# 128.net
KiCad netlist of a schematic drawn in EAGLE
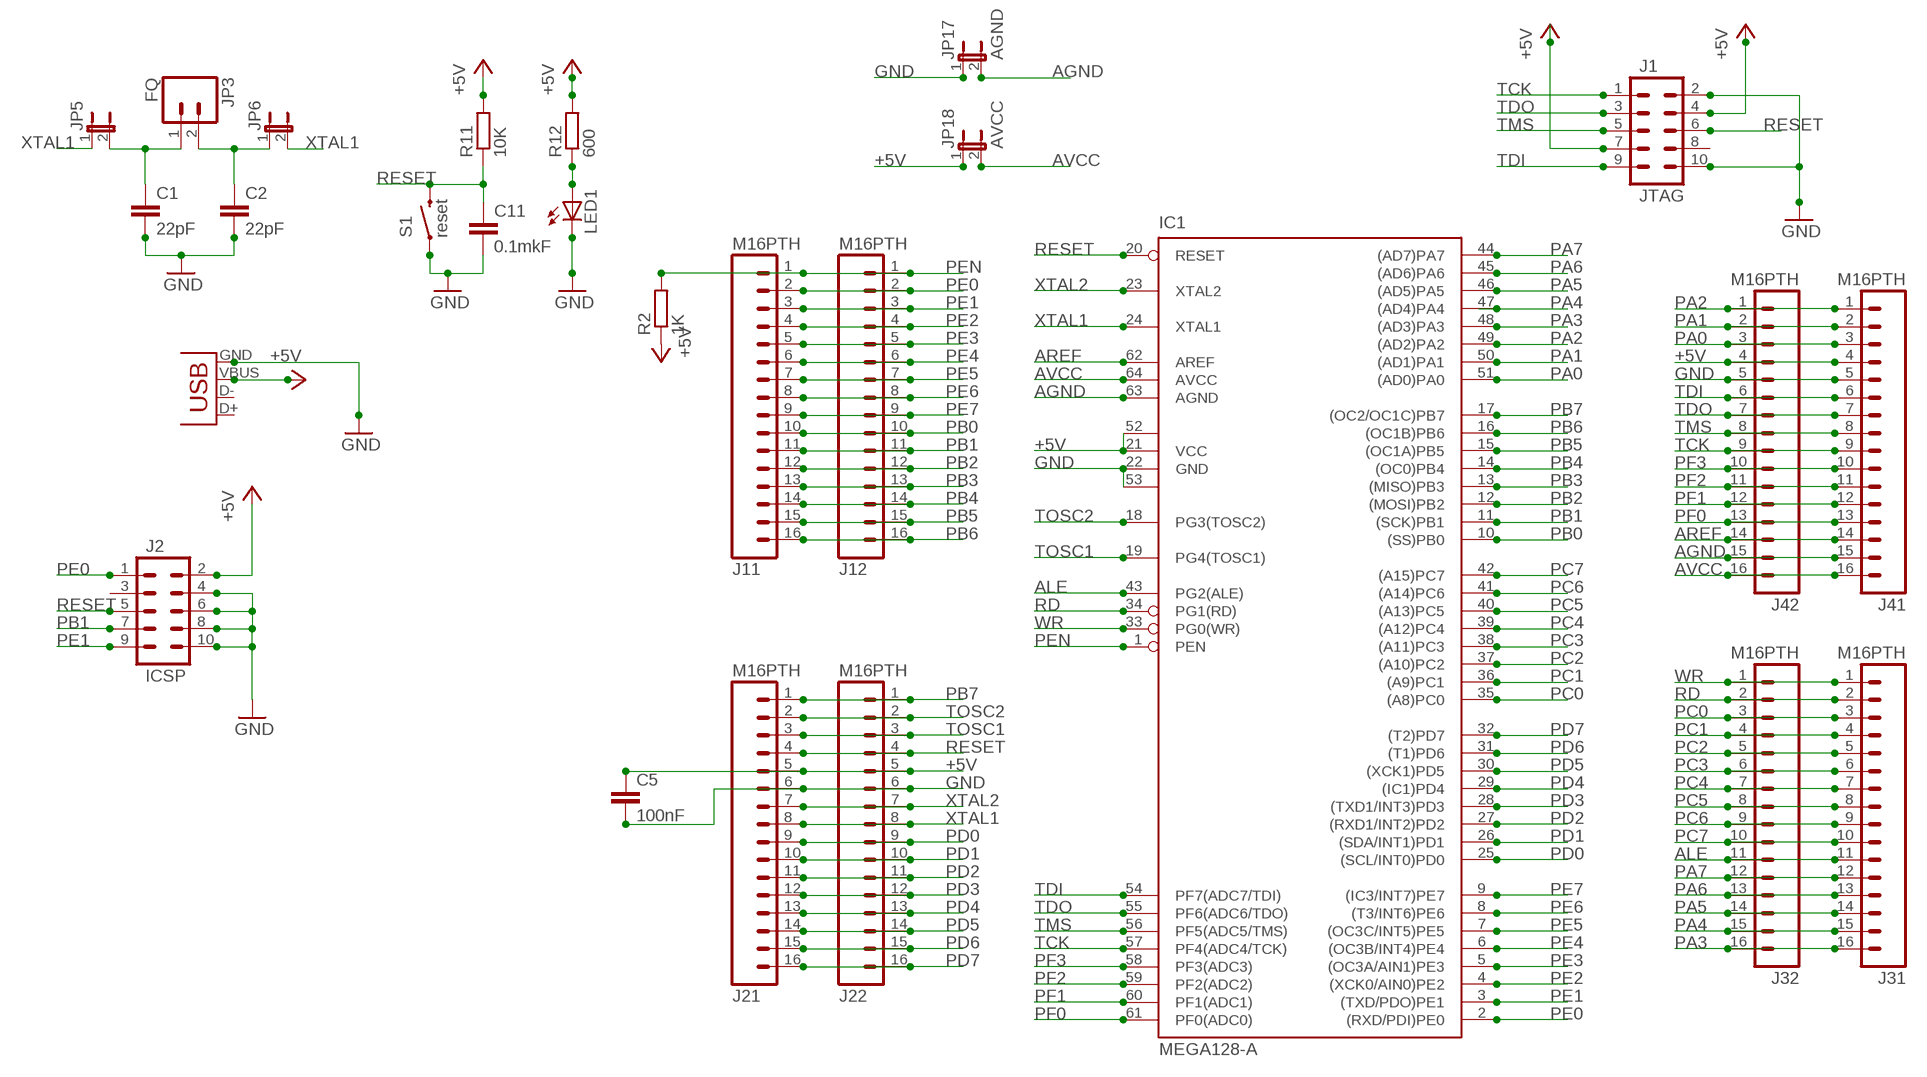
[diagram p0: schematic, sheet 1]

(export (version "E")
  (design (tool "Eeschema 10.0.6"))
  (components
    (comp (ref "C1")
      (value "22pF")
      (footprint "eagle-import:C0805")
      (libsource (lib "eagle-import") (part "C-EUC0805"))
    )
    (comp (ref "C2")
      (value "22pF")
      (footprint "eagle-import:C0805")
      (libsource (lib "eagle-import") (part "C-EUC0805"))
    )
    (comp (ref "C5")
      (value "100nF")
      (footprint "eagle-import:C0805")
      (libsource (lib "eagle-import") (part "C-EUC0805"))
    )
    (comp (ref "C11")
      (value "0.1mkF")
      (footprint "eagle-import:C0805")
      (libsource (lib "eagle-import") (part "C-EUC0805"))
    )
    (comp (ref "IC1")
      (value "MEGA128-A")
      (footprint "eagle-import:TQFP64")
      (libsource (lib "eagle-import") (part "MEGA128-A"))
    )
    (comp (ref "J1")
      (value "JTAG")
      (footprint "eagle-import:2X5-SHROUDED_LOCK")
      (libsource (lib "eagle-import") (part "M05X2SHD_LOCK"))
    )
    (comp (ref "J2")
      (value "ICSP")
      (footprint "eagle-import:2X5-SHROUDED_LOCK")
      (libsource (lib "eagle-import") (part "M05X2SHD_LOCK"))
    )
    (comp (ref "J11")
      (value "M16PTH")
      (footprint "eagle-import:1X16")
      (libsource (lib "eagle-import") (part "M16PTH"))
    )
    (comp (ref "J12")
      (value "M16PTH")
      (footprint "eagle-import:1X16")
      (libsource (lib "eagle-import") (part "M16PTH"))
    )
    (comp (ref "J21")
      (value "M16PTH")
      (footprint "eagle-import:1X16")
      (libsource (lib "eagle-import") (part "M16PTH"))
    )
    (comp (ref "J22")
      (value "M16PTH")
      (footprint "eagle-import:1X16")
      (libsource (lib "eagle-import") (part "M16PTH"))
    )
    (comp (ref "J31")
      (value "M16PTH")
      (footprint "eagle-import:1X16")
      (libsource (lib "eagle-import") (part "M16PTH"))
    )
    (comp (ref "J32")
      (value "M16PTH")
      (footprint "eagle-import:1X16")
      (libsource (lib "eagle-import") (part "M16PTH"))
    )
    (comp (ref "J41")
      (value "M16PTH")
      (footprint "eagle-import:1X16")
      (libsource (lib "eagle-import") (part "M16PTH"))
    )
    (comp (ref "J42")
      (value "M16PTH")
      (footprint "eagle-import:1X16")
      (libsource (lib "eagle-import") (part "M16PTH"))
    )
    (comp (ref "JP3")
      (value "FQ")
      (footprint "eagle-import:1X02_LOCK")
      (libsource (lib "eagle-import") (part "M02LOCK"))
    )
    (comp (ref "JP4")
      (value "USBSMD")
      (footprint "eagle-import:USB-MINIB")
      (libsource (lib "eagle-import") (part "USBSMD"))
    )
    (comp (ref "JP5")
      (value "JUMPER-2PTH")
      (footprint "eagle-import:1X02")
      (libsource (lib "eagle-import") (part "JUMPER-2PTH"))
    )
    (comp (ref "JP6")
      (value "JUMPER-2PTH")
      (footprint "eagle-import:1X02")
      (libsource (lib "eagle-import") (part "JUMPER-2PTH"))
    )
    (comp (ref "JP17")
      (value "AGND")
      (footprint "eagle-import:1X02")
      (libsource (lib "eagle-import") (part "JUMPER-2PTH"))
    )
    (comp (ref "JP18")
      (value "AVCC")
      (footprint "eagle-import:1X02")
      (libsource (lib "eagle-import") (part "JUMPER-2PTH"))
    )
    (comp (ref "LED1")
      (value "LED1206")
      (footprint "eagle-import:LED-1206")
      (libsource (lib "eagle-import") (part "LED1206"))
    )
    (comp (ref "R2")
      (value "1K")
      (footprint "eagle-import:R0805")
      (libsource (lib "eagle-import") (part "R-EU_R0805"))
    )
    (comp (ref "R11")
      (value "10K")
      (footprint "eagle-import:R0805")
      (libsource (lib "eagle-import") (part "R-EU_R0805"))
    )
    (comp (ref "R12")
      (value "600")
      (footprint "eagle-import:R0805")
      (libsource (lib "eagle-import") (part "R-EU_R0805"))
    )
    (comp (ref "S1")
      (value "reset")
      (footprint "eagle-import:TACTILE_SWITCH_SMD-2")
      (libsource (lib "eagle-import") (part "SWITCH-MOMENTARY-2SMD-2"))
    )
  )
  (nets
    (net (code "1") (name "+5V") (class "Default")
      (node (ref "C5") (pin "1") (pinfunction "1_1") (pintype "passive"))
      (node (ref "IC1") (pin "21") (pinfunction "VCC_21") (pintype "power_in"))
      (node (ref "IC1") (pin "52") (pinfunction "VCC1_52") (pintype "power_in"))
      (node (ref "J1") (pin "4") (pinfunction "4_4") (pintype "passive"))
      (node (ref "J1") (pin "7") (pinfunction "7_7") (pintype "passive"))
      (node (ref "J2") (pin "2") (pinfunction "2_2") (pintype "passive"))
      (node (ref "J21") (pin "5") (pinfunction "5_5") (pintype "passive"))
      (node (ref "J22") (pin "5") (pinfunction "5_5") (pintype "passive"))
      (node (ref "J41") (pin "4") (pinfunction "4_4") (pintype "passive"))
      (node (ref "J42") (pin "4") (pinfunction "4_4") (pintype "passive"))
      (node (ref "JP18") (pin "1") (pinfunction "1_1") (pintype "passive"))
      (node (ref "JP4") (pin "VBUS") (pinfunction "VBUS_VBUS") (pintype "bidirectional"))
      (node (ref "R11") (pin "2") (pinfunction "2_2") (pintype "passive"))
      (node (ref "R12") (pin "2") (pinfunction "2_2") (pintype "passive"))
      (node (ref "R2") (pin "1") (pinfunction "1_1") (pintype "passive"))
    )
    (net (code "2") (name "/AGND") (class "Default")
      (node (ref "IC1") (pin "63") (pinfunction "AGND_63") (pintype "bidirectional"))
      (node (ref "J41") (pin "15") (pinfunction "15_15") (pintype "passive"))
      (node (ref "J42") (pin "15") (pinfunction "15_15") (pintype "passive"))
      (node (ref "JP17") (pin "2") (pinfunction "2_2") (pintype "passive"))
    )
    (net (code "3") (name "/ALE") (class "Default")
      (node (ref "IC1") (pin "43") (pinfunction "PG2(ALE)_43") (pintype "bidirectional"))
      (node (ref "J31") (pin "11") (pinfunction "11_11") (pintype "passive"))
      (node (ref "J32") (pin "11") (pinfunction "11_11") (pintype "passive"))
    )
    (net (code "4") (name "/AREF") (class "Default")
      (node (ref "IC1") (pin "62") (pinfunction "AREF_62") (pintype "bidirectional"))
      (node (ref "J41") (pin "14") (pinfunction "14_14") (pintype "passive"))
      (node (ref "J42") (pin "14") (pinfunction "14_14") (pintype "passive"))
    )
    (net (code "5") (name "/AVCC") (class "Default")
      (node (ref "IC1") (pin "64") (pinfunction "AVCC_64") (pintype "bidirectional"))
      (node (ref "J41") (pin "16") (pinfunction "16_16") (pintype "passive"))
      (node (ref "J42") (pin "16") (pinfunction "16_16") (pintype "passive"))
      (node (ref "JP18") (pin "2") (pinfunction "2_2") (pintype "passive"))
    )
    (net (code "6") (name "/PA0") (class "Default")
      (node (ref "IC1") (pin "51") (pinfunction "(AD0)PA0_51") (pintype "bidirectional"))
      (node (ref "J41") (pin "3") (pinfunction "3_3") (pintype "passive"))
      (node (ref "J42") (pin "3") (pinfunction "3_3") (pintype "passive"))
    )
    (net (code "7") (name "/PA1") (class "Default")
      (node (ref "IC1") (pin "50") (pinfunction "(AD1)PA1_50") (pintype "bidirectional"))
      (node (ref "J41") (pin "2") (pinfunction "2_2") (pintype "passive"))
      (node (ref "J42") (pin "2") (pinfunction "2_2") (pintype "passive"))
    )
    (net (code "8") (name "/PA2") (class "Default")
      (node (ref "IC1") (pin "49") (pinfunction "(AD2)PA2_49") (pintype "bidirectional"))
      (node (ref "J41") (pin "1") (pinfunction "1_1") (pintype "passive"))
      (node (ref "J42") (pin "1") (pinfunction "1_1") (pintype "passive"))
    )
    (net (code "9") (name "/PA3") (class "Default")
      (node (ref "IC1") (pin "48") (pinfunction "(AD3)PA3_48") (pintype "bidirectional"))
      (node (ref "J31") (pin "16") (pinfunction "16_16") (pintype "passive"))
      (node (ref "J32") (pin "16") (pinfunction "16_16") (pintype "passive"))
    )
    (net (code "10") (name "/PA4") (class "Default")
      (node (ref "IC1") (pin "47") (pinfunction "(AD4)PA4_47") (pintype "bidirectional"))
      (node (ref "J31") (pin "15") (pinfunction "15_15") (pintype "passive"))
      (node (ref "J32") (pin "15") (pinfunction "15_15") (pintype "passive"))
    )
    (net (code "11") (name "/PA5") (class "Default")
      (node (ref "IC1") (pin "46") (pinfunction "(AD5)PA5_46") (pintype "bidirectional"))
      (node (ref "J31") (pin "14") (pinfunction "14_14") (pintype "passive"))
      (node (ref "J32") (pin "14") (pinfunction "14_14") (pintype "passive"))
    )
    (net (code "12") (name "/PA6") (class "Default")
      (node (ref "IC1") (pin "45") (pinfunction "(AD6)PA6_45") (pintype "bidirectional"))
      (node (ref "J31") (pin "13") (pinfunction "13_13") (pintype "passive"))
      (node (ref "J32") (pin "13") (pinfunction "13_13") (pintype "passive"))
    )
    (net (code "13") (name "/PA7") (class "Default")
      (node (ref "IC1") (pin "44") (pinfunction "(AD7)PA7_44") (pintype "bidirectional"))
      (node (ref "J31") (pin "12") (pinfunction "12_12") (pintype "passive"))
      (node (ref "J32") (pin "12") (pinfunction "12_12") (pintype "passive"))
    )
    (net (code "14") (name "/PB0") (class "Default")
      (node (ref "IC1") (pin "10") (pinfunction "(SS)PB0_10") (pintype "bidirectional"))
      (node (ref "J11") (pin "10") (pinfunction "10_10") (pintype "passive"))
      (node (ref "J12") (pin "10") (pinfunction "10_10") (pintype "passive"))
    )
    (net (code "15") (name "/PB1") (class "Default")
      (node (ref "IC1") (pin "11") (pinfunction "(SCK)PB1_11") (pintype "bidirectional"))
      (node (ref "J11") (pin "11") (pinfunction "11_11") (pintype "passive"))
      (node (ref "J12") (pin "11") (pinfunction "11_11") (pintype "passive"))
      (node (ref "J2") (pin "7") (pinfunction "7_7") (pintype "passive"))
    )
    (net (code "16") (name "/PB2") (class "Default")
      (node (ref "IC1") (pin "12") (pinfunction "(MOSI)PB2_12") (pintype "bidirectional"))
      (node (ref "J11") (pin "12") (pinfunction "12_12") (pintype "passive"))
      (node (ref "J12") (pin "12") (pinfunction "12_12") (pintype "passive"))
    )
    (net (code "17") (name "/PB3") (class "Default")
      (node (ref "IC1") (pin "13") (pinfunction "(MISO)PB3_13") (pintype "bidirectional"))
      (node (ref "J11") (pin "13") (pinfunction "13_13") (pintype "passive"))
      (node (ref "J12") (pin "13") (pinfunction "13_13") (pintype "passive"))
    )
    (net (code "18") (name "/PB4") (class "Default")
      (node (ref "IC1") (pin "14") (pinfunction "(OC0)PB4_14") (pintype "bidirectional"))
      (node (ref "J11") (pin "14") (pinfunction "14_14") (pintype "passive"))
      (node (ref "J12") (pin "14") (pinfunction "14_14") (pintype "passive"))
    )
    (net (code "19") (name "/PB5") (class "Default")
      (node (ref "IC1") (pin "15") (pinfunction "(OC1A)PB5_15") (pintype "bidirectional"))
      (node (ref "J11") (pin "15") (pinfunction "15_15") (pintype "passive"))
      (node (ref "J12") (pin "15") (pinfunction "15_15") (pintype "passive"))
    )
    (net (code "20") (name "/PB6") (class "Default")
      (node (ref "IC1") (pin "16") (pinfunction "(OC1B)PB6_16") (pintype "bidirectional"))
      (node (ref "J11") (pin "16") (pinfunction "16_16") (pintype "passive"))
      (node (ref "J12") (pin "16") (pinfunction "16_16") (pintype "passive"))
    )
    (net (code "21") (name "/PB7") (class "Default")
      (node (ref "IC1") (pin "17") (pinfunction "(OC2/OC1C)PB7_17") (pintype "bidirectional"))
      (node (ref "J21") (pin "1") (pinfunction "1_1") (pintype "passive"))
      (node (ref "J22") (pin "1") (pinfunction "1_1") (pintype "passive"))
    )
    (net (code "22") (name "/PC0") (class "Default")
      (node (ref "IC1") (pin "35") (pinfunction "(A8)PC0_35") (pintype "output"))
      (node (ref "J31") (pin "3") (pinfunction "3_3") (pintype "passive"))
      (node (ref "J32") (pin "3") (pinfunction "3_3") (pintype "passive"))
    )
    (net (code "23") (name "/PC1") (class "Default")
      (node (ref "IC1") (pin "36") (pinfunction "(A9)PC1_36") (pintype "output"))
      (node (ref "J31") (pin "4") (pinfunction "4_4") (pintype "passive"))
      (node (ref "J32") (pin "4") (pinfunction "4_4") (pintype "passive"))
    )
    (net (code "24") (name "/PC2") (class "Default")
      (node (ref "IC1") (pin "37") (pinfunction "(A10)PC2_37") (pintype "output"))
      (node (ref "J31") (pin "5") (pinfunction "5_5") (pintype "passive"))
      (node (ref "J32") (pin "5") (pinfunction "5_5") (pintype "passive"))
    )
    (net (code "25") (name "/PC3") (class "Default")
      (node (ref "IC1") (pin "38") (pinfunction "(A11)PC3_38") (pintype "output"))
      (node (ref "J31") (pin "6") (pinfunction "6_6") (pintype "passive"))
      (node (ref "J32") (pin "6") (pinfunction "6_6") (pintype "passive"))
    )
    (net (code "26") (name "/PC4") (class "Default")
      (node (ref "IC1") (pin "39") (pinfunction "(A12)PC4_39") (pintype "output"))
      (node (ref "J31") (pin "7") (pinfunction "7_7") (pintype "passive"))
      (node (ref "J32") (pin "7") (pinfunction "7_7") (pintype "passive"))
    )
    (net (code "27") (name "/PC5") (class "Default")
      (node (ref "IC1") (pin "40") (pinfunction "(A13)PC5_40") (pintype "output"))
      (node (ref "J31") (pin "8") (pinfunction "8_8") (pintype "passive"))
      (node (ref "J32") (pin "8") (pinfunction "8_8") (pintype "passive"))
    )
    (net (code "28") (name "/PC6") (class "Default")
      (node (ref "IC1") (pin "41") (pinfunction "(A14)PC6_41") (pintype "output"))
      (node (ref "J31") (pin "9") (pinfunction "9_9") (pintype "passive"))
      (node (ref "J32") (pin "9") (pinfunction "9_9") (pintype "passive"))
    )
    (net (code "29") (name "/PC7") (class "Default")
      (node (ref "IC1") (pin "42") (pinfunction "(A15)PC7_42") (pintype "output"))
      (node (ref "J31") (pin "10") (pinfunction "10_10") (pintype "passive"))
      (node (ref "J32") (pin "10") (pinfunction "10_10") (pintype "passive"))
    )
    (net (code "30") (name "/PD0") (class "Default")
      (node (ref "IC1") (pin "25") (pinfunction "(SCL/INT0)PD0_25") (pintype "bidirectional"))
      (node (ref "J21") (pin "9") (pinfunction "9_9") (pintype "passive"))
      (node (ref "J22") (pin "9") (pinfunction "9_9") (pintype "passive"))
    )
    (net (code "31") (name "/PD1") (class "Default")
      (node (ref "IC1") (pin "26") (pinfunction "(SDA/INT1)PD1_26") (pintype "bidirectional"))
      (node (ref "J21") (pin "10") (pinfunction "10_10") (pintype "passive"))
      (node (ref "J22") (pin "10") (pinfunction "10_10") (pintype "passive"))
    )
    (net (code "32") (name "/PD2") (class "Default")
      (node (ref "IC1") (pin "27") (pinfunction "(RXD1/INT2)PD2_27") (pintype "bidirectional"))
      (node (ref "J21") (pin "11") (pinfunction "11_11") (pintype "passive"))
      (node (ref "J22") (pin "11") (pinfunction "11_11") (pintype "passive"))
    )
    (net (code "33") (name "/PD3") (class "Default")
      (node (ref "IC1") (pin "28") (pinfunction "(TXD1/INT3)PD3_28") (pintype "bidirectional"))
      (node (ref "J21") (pin "12") (pinfunction "12_12") (pintype "passive"))
      (node (ref "J22") (pin "12") (pinfunction "12_12") (pintype "passive"))
    )
    (net (code "34") (name "/PD4") (class "Default")
      (node (ref "IC1") (pin "29") (pinfunction "(IC1)PD4_29") (pintype "bidirectional"))
      (node (ref "J21") (pin "13") (pinfunction "13_13") (pintype "passive"))
      (node (ref "J22") (pin "13") (pinfunction "13_13") (pintype "passive"))
    )
    (net (code "35") (name "/PD5") (class "Default")
      (node (ref "IC1") (pin "30") (pinfunction "(XCK1)PD5_30") (pintype "bidirectional"))
      (node (ref "J21") (pin "14") (pinfunction "14_14") (pintype "passive"))
      (node (ref "J22") (pin "14") (pinfunction "14_14") (pintype "passive"))
    )
    (net (code "36") (name "/PD6") (class "Default")
      (node (ref "IC1") (pin "31") (pinfunction "(T1)PD6_31") (pintype "bidirectional"))
      (node (ref "J21") (pin "15") (pinfunction "15_15") (pintype "passive"))
      (node (ref "J22") (pin "15") (pinfunction "15_15") (pintype "passive"))
    )
    (net (code "37") (name "/PD7") (class "Default")
      (node (ref "IC1") (pin "32") (pinfunction "(T2)PD7_32") (pintype "bidirectional"))
      (node (ref "J21") (pin "16") (pinfunction "16_16") (pintype "passive"))
      (node (ref "J22") (pin "16") (pinfunction "16_16") (pintype "passive"))
    )
    (net (code "38") (name "/PE0") (class "Default")
      (node (ref "IC1") (pin "2") (pinfunction "(RXD/PDI)PE0_2") (pintype "bidirectional"))
      (node (ref "J11") (pin "2") (pinfunction "2_2") (pintype "passive"))
      (node (ref "J12") (pin "2") (pinfunction "2_2") (pintype "passive"))
      (node (ref "J2") (pin "1") (pinfunction "1_1") (pintype "passive"))
    )
    (net (code "39") (name "/PE1") (class "Default")
      (node (ref "IC1") (pin "3") (pinfunction "(TXD/PDO)PE1_3") (pintype "bidirectional"))
      (node (ref "J11") (pin "3") (pinfunction "3_3") (pintype "passive"))
      (node (ref "J12") (pin "3") (pinfunction "3_3") (pintype "passive"))
      (node (ref "J2") (pin "9") (pinfunction "9_9") (pintype "passive"))
    )
    (net (code "40") (name "/PE2") (class "Default")
      (node (ref "IC1") (pin "4") (pinfunction "(XCK0/AIN0)PE2_4") (pintype "bidirectional"))
      (node (ref "J11") (pin "4") (pinfunction "4_4") (pintype "passive"))
      (node (ref "J12") (pin "4") (pinfunction "4_4") (pintype "passive"))
    )
    (net (code "41") (name "/PE3") (class "Default")
      (node (ref "IC1") (pin "5") (pinfunction "(OC3A/AIN1)PE3_5") (pintype "bidirectional"))
      (node (ref "J11") (pin "5") (pinfunction "5_5") (pintype "passive"))
      (node (ref "J12") (pin "5") (pinfunction "5_5") (pintype "passive"))
    )
    (net (code "42") (name "/PE4") (class "Default")
      (node (ref "IC1") (pin "6") (pinfunction "(OC3B/INT4)PE4_6") (pintype "bidirectional"))
      (node (ref "J11") (pin "6") (pinfunction "6_6") (pintype "passive"))
      (node (ref "J12") (pin "6") (pinfunction "6_6") (pintype "passive"))
    )
    (net (code "43") (name "/PE5") (class "Default")
      (node (ref "IC1") (pin "7") (pinfunction "(OC3C/INT5)PE5_7") (pintype "bidirectional"))
      (node (ref "J11") (pin "7") (pinfunction "7_7") (pintype "passive"))
      (node (ref "J12") (pin "7") (pinfunction "7_7") (pintype "passive"))
    )
    (net (code "44") (name "/PE6") (class "Default")
      (node (ref "IC1") (pin "8") (pinfunction "(T3/INT6)PE6_8") (pintype "bidirectional"))
      (node (ref "J11") (pin "8") (pinfunction "8_8") (pintype "passive"))
      (node (ref "J12") (pin "8") (pinfunction "8_8") (pintype "passive"))
    )
    (net (code "45") (name "/PE7") (class "Default")
      (node (ref "IC1") (pin "9") (pinfunction "(IC3/INT7)PE7_9") (pintype "bidirectional"))
      (node (ref "J11") (pin "9") (pinfunction "9_9") (pintype "passive"))
      (node (ref "J12") (pin "9") (pinfunction "9_9") (pintype "passive"))
    )
    (net (code "46") (name "/PEN") (class "Default")
      (node (ref "IC1") (pin "1") (pinfunction "PEN_1") (pintype "input"))
      (node (ref "J11") (pin "1") (pinfunction "1_1") (pintype "passive"))
      (node (ref "J12") (pin "1") (pinfunction "1_1") (pintype "passive"))
      (node (ref "R2") (pin "2") (pinfunction "2_2") (pintype "passive"))
    )
    (net (code "47") (name "/PF0") (class "Default")
      (node (ref "IC1") (pin "61") (pinfunction "PF0(ADC0)_61") (pintype "input"))
      (node (ref "J41") (pin "13") (pinfunction "13_13") (pintype "passive"))
      (node (ref "J42") (pin "13") (pinfunction "13_13") (pintype "passive"))
    )
    (net (code "48") (name "/PF1") (class "Default")
      (node (ref "IC1") (pin "60") (pinfunction "PF1(ADC1)_60") (pintype "input"))
      (node (ref "J41") (pin "12") (pinfunction "12_12") (pintype "passive"))
      (node (ref "J42") (pin "12") (pinfunction "12_12") (pintype "passive"))
    )
    (net (code "49") (name "/PF2") (class "Default")
      (node (ref "IC1") (pin "59") (pinfunction "PF2(ADC2)_59") (pintype "input"))
      (node (ref "J41") (pin "11") (pinfunction "11_11") (pintype "passive"))
      (node (ref "J42") (pin "11") (pinfunction "11_11") (pintype "passive"))
    )
    (net (code "50") (name "/PF3") (class "Default")
      (node (ref "IC1") (pin "58") (pinfunction "PF3(ADC3)_58") (pintype "input"))
      (node (ref "J41") (pin "10") (pinfunction "10_10") (pintype "passive"))
      (node (ref "J42") (pin "10") (pinfunction "10_10") (pintype "passive"))
    )
    (net (code "51") (name "/RD") (class "Default")
      (node (ref "IC1") (pin "34") (pinfunction "PG1(RD)_34") (pintype "bidirectional"))
      (node (ref "J31") (pin "2") (pinfunction "2_2") (pintype "passive"))
      (node (ref "J32") (pin "2") (pinfunction "2_2") (pintype "passive"))
    )
    (net (code "52") (name "/RESET") (class "Default")
      (node (ref "C11") (pin "1") (pinfunction "1_1") (pintype "passive"))
      (node (ref "IC1") (pin "20") (pinfunction "RESET_20") (pintype "input"))
      (node (ref "J1") (pin "6") (pinfunction "6_6") (pintype "passive"))
      (node (ref "J2") (pin "5") (pinfunction "5_5") (pintype "passive"))
      (node (ref "J21") (pin "4") (pinfunction "4_4") (pintype "passive"))
      (node (ref "J22") (pin "4") (pinfunction "4_4") (pintype "passive"))
      (node (ref "R11") (pin "1") (pinfunction "1_1") (pintype "passive"))
      (node (ref "S1") (pin "1") (pinfunction "2_1") (pintype "passive"))
    )
    (net (code "53") (name "/TCK") (class "Default")
      (node (ref "IC1") (pin "57") (pinfunction "PF4(ADC4/TCK)_57") (pintype "input"))
      (node (ref "J1") (pin "1") (pinfunction "1_1") (pintype "passive"))
      (node (ref "J41") (pin "9") (pinfunction "9_9") (pintype "passive"))
      (node (ref "J42") (pin "9") (pinfunction "9_9") (pintype "passive"))
    )
    (net (code "54") (name "/TDI") (class "Default")
      (node (ref "IC1") (pin "54") (pinfunction "PF7(ADC7/TDI)_54") (pintype "input"))
      (node (ref "J1") (pin "9") (pinfunction "9_9") (pintype "passive"))
      (node (ref "J41") (pin "6") (pinfunction "6_6") (pintype "passive"))
      (node (ref "J42") (pin "6") (pinfunction "6_6") (pintype "passive"))
    )
    (net (code "55") (name "/TDO") (class "Default")
      (node (ref "IC1") (pin "55") (pinfunction "PF6(ADC6/TDO)_55") (pintype "input"))
      (node (ref "J1") (pin "3") (pinfunction "3_3") (pintype "passive"))
      (node (ref "J41") (pin "7") (pinfunction "7_7") (pintype "passive"))
      (node (ref "J42") (pin "7") (pinfunction "7_7") (pintype "passive"))
    )
    (net (code "56") (name "/TMS") (class "Default")
      (node (ref "IC1") (pin "56") (pinfunction "PF5(ADC5/TMS)_56") (pintype "input"))
      (node (ref "J1") (pin "5") (pinfunction "5_5") (pintype "passive"))
      (node (ref "J41") (pin "8") (pinfunction "8_8") (pintype "passive"))
      (node (ref "J42") (pin "8") (pinfunction "8_8") (pintype "passive"))
    )
    (net (code "57") (name "/TOSC1") (class "Default")
      (node (ref "IC1") (pin "19") (pinfunction "PG4(TOSC1)_19") (pintype "bidirectional"))
      (node (ref "J21") (pin "3") (pinfunction "3_3") (pintype "passive"))
      (node (ref "J22") (pin "3") (pinfunction "3_3") (pintype "passive"))
    )
    (net (code "58") (name "/TOSC2") (class "Default")
      (node (ref "IC1") (pin "18") (pinfunction "PG3(TOSC2)_18") (pintype "bidirectional"))
      (node (ref "J21") (pin "2") (pinfunction "2_2") (pintype "passive"))
      (node (ref "J22") (pin "2") (pinfunction "2_2") (pintype "passive"))
    )
    (net (code "59") (name "/WR") (class "Default")
      (node (ref "IC1") (pin "33") (pinfunction "PG0(WR)_33") (pintype "bidirectional"))
      (node (ref "J31") (pin "1") (pinfunction "1_1") (pintype "passive"))
      (node (ref "J32") (pin "1") (pinfunction "1_1") (pintype "passive"))
    )
    (net (code "60") (name "/XTAL1") (class "Default")
      (node (ref "IC1") (pin "24") (pinfunction "XTAL1_24") (pintype "bidirectional"))
      (node (ref "J21") (pin "8") (pinfunction "8_8") (pintype "passive"))
      (node (ref "J22") (pin "8") (pinfunction "8_8") (pintype "passive"))
      (node (ref "JP5") (pin "1") (pinfunction "1_1") (pintype "passive"))
      (node (ref "JP6") (pin "2") (pinfunction "2_2") (pintype "passive"))
    )
    (net (code "61") (name "/XTAL2") (class "Default")
      (node (ref "IC1") (pin "23") (pinfunction "XTAL2_23") (pintype "bidirectional"))
      (node (ref "J21") (pin "7") (pinfunction "7_7") (pintype "passive"))
      (node (ref "J22") (pin "7") (pinfunction "7_7") (pintype "passive"))
    )
    (net (code "62") (name "GND") (class "Default")
      (node (ref "C1") (pin "2") (pinfunction "2_2") (pintype "passive"))
      (node (ref "C11") (pin "2") (pinfunction "2_2") (pintype "passive"))
      (node (ref "C2") (pin "2") (pinfunction "2_2") (pintype "passive"))
      (node (ref "C5") (pin "2") (pinfunction "2_2") (pintype "passive"))
      (node (ref "IC1") (pin "22") (pinfunction "GND_22") (pintype "power_in"))
      (node (ref "IC1") (pin "53") (pinfunction "GND1_53") (pintype "power_in"))
      (node (ref "J1") (pin "10") (pinfunction "10_10") (pintype "passive"))
      (node (ref "J1") (pin "2") (pinfunction "2_2") (pintype "passive"))
      (node (ref "J2") (pin "10") (pinfunction "10_10") (pintype "passive"))
      (node (ref "J2") (pin "4") (pinfunction "4_4") (pintype "passive"))
      (node (ref "J2") (pin "6") (pinfunction "6_6") (pintype "passive"))
      (node (ref "J2") (pin "8") (pinfunction "8_8") (pintype "passive"))
      (node (ref "J21") (pin "6") (pinfunction "6_6") (pintype "passive"))
      (node (ref "J22") (pin "6") (pinfunction "6_6") (pintype "passive"))
      (node (ref "J41") (pin "5") (pinfunction "5_5") (pintype "passive"))
      (node (ref "J42") (pin "5") (pinfunction "5_5") (pintype "passive"))
      (node (ref "JP17") (pin "1") (pinfunction "1_1") (pintype "passive"))
      (node (ref "JP4") (pin "GND") (pinfunction "GND_GND") (pintype "bidirectional"))
      (node (ref "LED1") (pin "C") (pinfunction "C_C") (pintype "passive"))
      (node (ref "S1") (pin "2") (pinfunction "1_2") (pintype "passive"))
    )
    (net (code "63") (name "Net-(C1-Pad1)") (class "Default")
      (node (ref "C1") (pin "1") (pinfunction "1_1") (pintype "passive"))
      (node (ref "JP3") (pin "1") (pinfunction "1_1") (pintype "passive"))
      (node (ref "JP5") (pin "2") (pinfunction "2_2") (pintype "passive"))
    )
    (net (code "64") (name "Net-(C2-Pad1)") (class "Default")
      (node (ref "C2") (pin "1") (pinfunction "1_1") (pintype "passive"))
      (node (ref "JP3") (pin "2") (pinfunction "2_2") (pintype "passive"))
      (node (ref "JP6") (pin "1") (pinfunction "1_1") (pintype "passive"))
    )
    (net (code "65") (name "Net-(LED1-PadA)") (class "Default")
      (node (ref "LED1") (pin "A") (pinfunction "A_A") (pintype "passive"))
      (node (ref "R12") (pin "1") (pinfunction "1_1") (pintype "passive"))
    )
    (net (code "66") (name "unconnected-(J1-Pad8)") (class "Default")
      (node (ref "J1") (pin "8") (pinfunction "8_8") (pintype "passive"))
    )
    (net (code "67") (name "unconnected-(J2-Pad3)") (class "Default")
      (node (ref "J2") (pin "3") (pinfunction "3_3") (pintype "passive"))
    )
    (net (code "68") (name "unconnected-(JP4-PadD+)") (class "Default")
      (node (ref "JP4") (pin "D+") (pinfunction "D+_D+") (pintype "bidirectional"))
    )
    (net (code "69") (name "unconnected-(JP4-PadD-)") (class "Default")
      (node (ref "JP4") (pin "D-") (pinfunction "D-_D-") (pintype "bidirectional"))
    )
  )
)
